# 3.net
KiCad netlist of a schematic drawn in Altium Designer
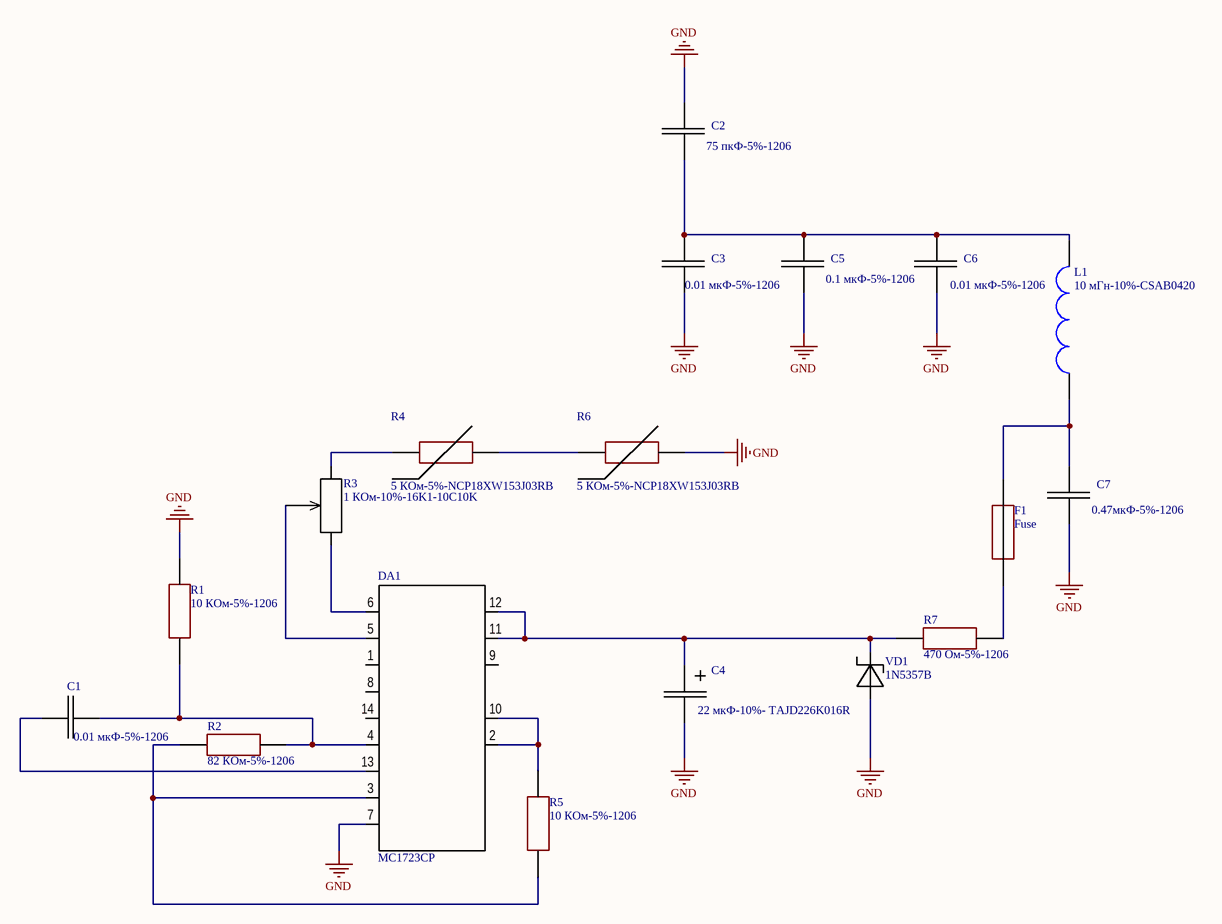
[diagram p0: Э3.SchDoc]

(export (version "E")
  (design (tool "Eeschema 10.0.6"))
  (components
    (comp (ref "C1")
      (value "0.01 мкФ-5%-1206")
      (footprint "1206_cond")
      (libsource (lib "MyLib") (part "Cap_1206C"))
    )
    (comp (ref "C2")
      (value "75 пкФ-5%-1206")
      (footprint "1206_cond")
      (libsource (lib "MyLib") (part "Cap_1206C"))
    )
    (comp (ref "C3")
      (value "0.01 мкФ-5%-1206")
      (footprint "1206_cond")
      (libsource (lib "MyLib") (part "Cap_1206C"))
    )
    (comp (ref "C4")
      (value "22 мкФ-10%- TAJD226K016R")
      (footprint "TAJD")
      (libsource (lib "MyLib") (part "Cap_pol"))
    )
    (comp (ref "C5")
      (value "0.1 мкФ-5%-1206")
      (footprint "1206_cond")
      (libsource (lib "MyLib") (part "Cap_1206C"))
    )
    (comp (ref "C6")
      (value "0.01 мкФ-5%-1206")
      (footprint "1206_cond")
      (libsource (lib "MyLib") (part "Cap_1206C"))
    )
    (comp (ref "C7")
      (value "0.47мкФ-5%-1206")
      (footprint "1206_cond")
      (libsource (lib "MyLib") (part "Cap_1206C"))
    )
    (comp (ref "DA1") (value "MC1723CP") (footprint "SOIC-14") (libsource (lib "MyLib") (part "MC1723CP")))
    (comp (ref "F1") (value "Fuse") (footprint "F1") (libsource (lib "MyLib") (part "F1")))
    (comp (ref "L1")
      (value "10 мГн-10%-CSAB0420")
      (footprint "Ind")
      (libsource (lib "MyLib") (part "Inductor_0603L"))
    )
    (comp (ref "R1")
      (value "10 КОм-5%-1206")
      (footprint "1206")
      (libsource (lib "") (part "Resistor 1206R_1"))
    )
    (comp (ref "R2")
      (value "82 КОм-5%-1206")
      (footprint "1206")
      (libsource (lib "MyLib") (part "Resistor 1206R"))
    )
    (comp (ref "R3")
      (value "1 КОм-10%-16K1-10C10K")
      (footprint "16K1")
      (libsource (lib "MyLib") (part "Resistor_per"))
    )
    (comp (ref "R4")
      (value "5 КОм-5%-NCP18XW153J03RB")
      (footprint "Term")
      (libsource (lib "MyLib") (part "Term"))
    )
    (comp (ref "R5")
      (value "10 КОм-5%-1206")
      (footprint "1206")
      (libsource (lib "") (part "Resistor 1206R_1"))
    )
    (comp (ref "R6")
      (value "5 КОм-5%-NCP18XW153J03RB")
      (footprint "Term")
      (libsource (lib "MyLib") (part "Term"))
    )
    (comp (ref "R7")
      (value "470 Ом-5%-1206")
      (footprint "1206")
      (libsource (lib "MyLib") (part "Resistor 1206R"))
    )
    (comp (ref "VD1") (value "1N5357B") (footprint "Stab") (libsource (lib "MyLib") (part "Stab")))
  )
  (nets
    (net (code "1") (name "GND") (class "Default")
      (node (ref "C2") (pin "1") (pinfunction "1_1") (pintype "passive"))
      (node (ref "C3") (pin "0") (pinfunction "0_0") (pintype "passive"))
      (node (ref "C4") (pin "1") (pinfunction "1_1") (pintype "passive"))
      (node (ref "C5") (pin "0") (pinfunction "0_0") (pintype "passive"))
      (node (ref "C6") (pin "0") (pinfunction "0_0") (pintype "passive"))
      (node (ref "C7") (pin "0") (pinfunction "0_0") (pintype "passive"))
      (node (ref "DA1") (pin "7") (pinfunction "7_7") (pintype "passive"))
      (node (ref "R1") (pin "1") (pinfunction "1_1") (pintype "passive"))
      (node (ref "R6") (pin "1") (pinfunction "1_1") (pintype "passive"))
      (node (ref "VD1") (pin "0") (pinfunction "0_0") (pintype "passive"))
    )
    (net (code "2") (name "Net-(C1-Pad0)") (class "Default")
      (node (ref "C1") (pin "0") (pinfunction "0_0") (pintype "passive"))
      (node (ref "DA1") (pin "13") (pinfunction "13_13") (pintype "passive"))
    )
    (net (code "3") (name "Net-(C1-Pad1)") (class "Default")
      (node (ref "C1") (pin "1") (pinfunction "1_1") (pintype "passive"))
      (node (ref "DA1") (pin "4") (pinfunction "4_4") (pintype "passive"))
      (node (ref "R1") (pin "0") (pinfunction "0_0") (pintype "passive"))
      (node (ref "R2") (pin "1") (pinfunction "1_1") (pintype "passive"))
    )
    (net (code "4") (name "Net-(C2-Pad0)") (class "Default")
      (node (ref "C2") (pin "0") (pinfunction "0_0") (pintype "passive"))
      (node (ref "C3") (pin "1") (pinfunction "1_1") (pintype "passive"))
      (node (ref "C5") (pin "1") (pinfunction "1_1") (pintype "passive"))
      (node (ref "C6") (pin "1") (pinfunction "1_1") (pintype "passive"))
      (node (ref "L1") (pin "1") (pinfunction "1_1") (pintype "passive"))
    )
    (net (code "5") (name "Net-(C4-Pad0)") (class "Default")
      (node (ref "C4") (pin "0") (pinfunction "0_0") (pintype "passive"))
      (node (ref "DA1") (pin "11") (pinfunction "11_11") (pintype "passive"))
      (node (ref "DA1") (pin "12") (pinfunction "12_12") (pintype "passive"))
      (node (ref "R7") (pin "0") (pinfunction "0_0") (pintype "passive"))
      (node (ref "VD1") (pin "1") (pinfunction "1_1") (pintype "passive"))
    )
    (net (code "6") (name "Net-(C7-Pad1)") (class "Default")
      (node (ref "C7") (pin "1") (pinfunction "1_1") (pintype "passive"))
      (node (ref "F1") (pin "1") (pinfunction "1_1") (pintype "passive"))
      (node (ref "L1") (pin "0") (pinfunction "0_0") (pintype "passive"))
    )
    (net (code "7") (name "Net-(DA1-Pad3)") (class "Default")
      (node (ref "DA1") (pin "3") (pinfunction "3_3") (pintype "passive"))
      (node (ref "R2") (pin "0") (pinfunction "0_0") (pintype "passive"))
      (node (ref "R5") (pin "0") (pinfunction "0_0") (pintype "passive"))
    )
    (net (code "8") (name "Net-(DA1-Pad5)") (class "Default")
      (node (ref "DA1") (pin "5") (pinfunction "5_5") (pintype "passive"))
      (node (ref "R3") (pin "3") (pinfunction "3_3") (pintype "passive"))
    )
    (net (code "9") (name "Net-(DA1-Pad6)") (class "Default")
      (node (ref "DA1") (pin "6") (pinfunction "6_6") (pintype "passive"))
      (node (ref "R3") (pin "1") (pinfunction "1_1") (pintype "passive"))
    )
    (net (code "10") (name "Net-(DA1-Pad10)") (class "Default")
      (node (ref "DA1") (pin "10") (pinfunction "10_10") (pintype "passive"))
      (node (ref "DA1") (pin "2") (pinfunction "2_2") (pintype "passive"))
      (node (ref "R5") (pin "1") (pinfunction "1_1") (pintype "passive"))
    )
    (net (code "11") (name "Net-(F1-Pad0)") (class "Default")
      (node (ref "F1") (pin "0") (pinfunction "0_0") (pintype "passive"))
      (node (ref "R7") (pin "1") (pinfunction "1_1") (pintype "passive"))
    )
    (net (code "12") (name "Net-(R3-Pad2)") (class "Default")
      (node (ref "R3") (pin "2") (pinfunction "2_2") (pintype "passive"))
      (node (ref "R4") (pin "0") (pinfunction "0_0") (pintype "passive"))
    )
    (net (code "13") (name "Net-(R4-Pad1)") (class "Default")
      (node (ref "R4") (pin "1") (pinfunction "1_1") (pintype "passive"))
      (node (ref "R6") (pin "0") (pinfunction "0_0") (pintype "passive"))
    )
    (net (code "14") (name "unconnected-(DA1-Pad1)") (class "Default")
      (node (ref "DA1") (pin "1") (pinfunction "1_1") (pintype "passive"))
    )
    (net (code "15") (name "unconnected-(DA1-Pad8)") (class "Default")
      (node (ref "DA1") (pin "8") (pinfunction "8_8") (pintype "passive"))
    )
    (net (code "16") (name "unconnected-(DA1-Pad9)") (class "Default")
      (node (ref "DA1") (pin "9") (pinfunction "9_9") (pintype "passive"))
    )
    (net (code "17") (name "unconnected-(DA1-Pad14)") (class "Default")
      (node (ref "DA1") (pin "14") (pinfunction "14_14") (pintype "passive"))
    )
  )
)
